# RFID_Brd.net
KiCad netlist of a schematic drawn in EAGLE
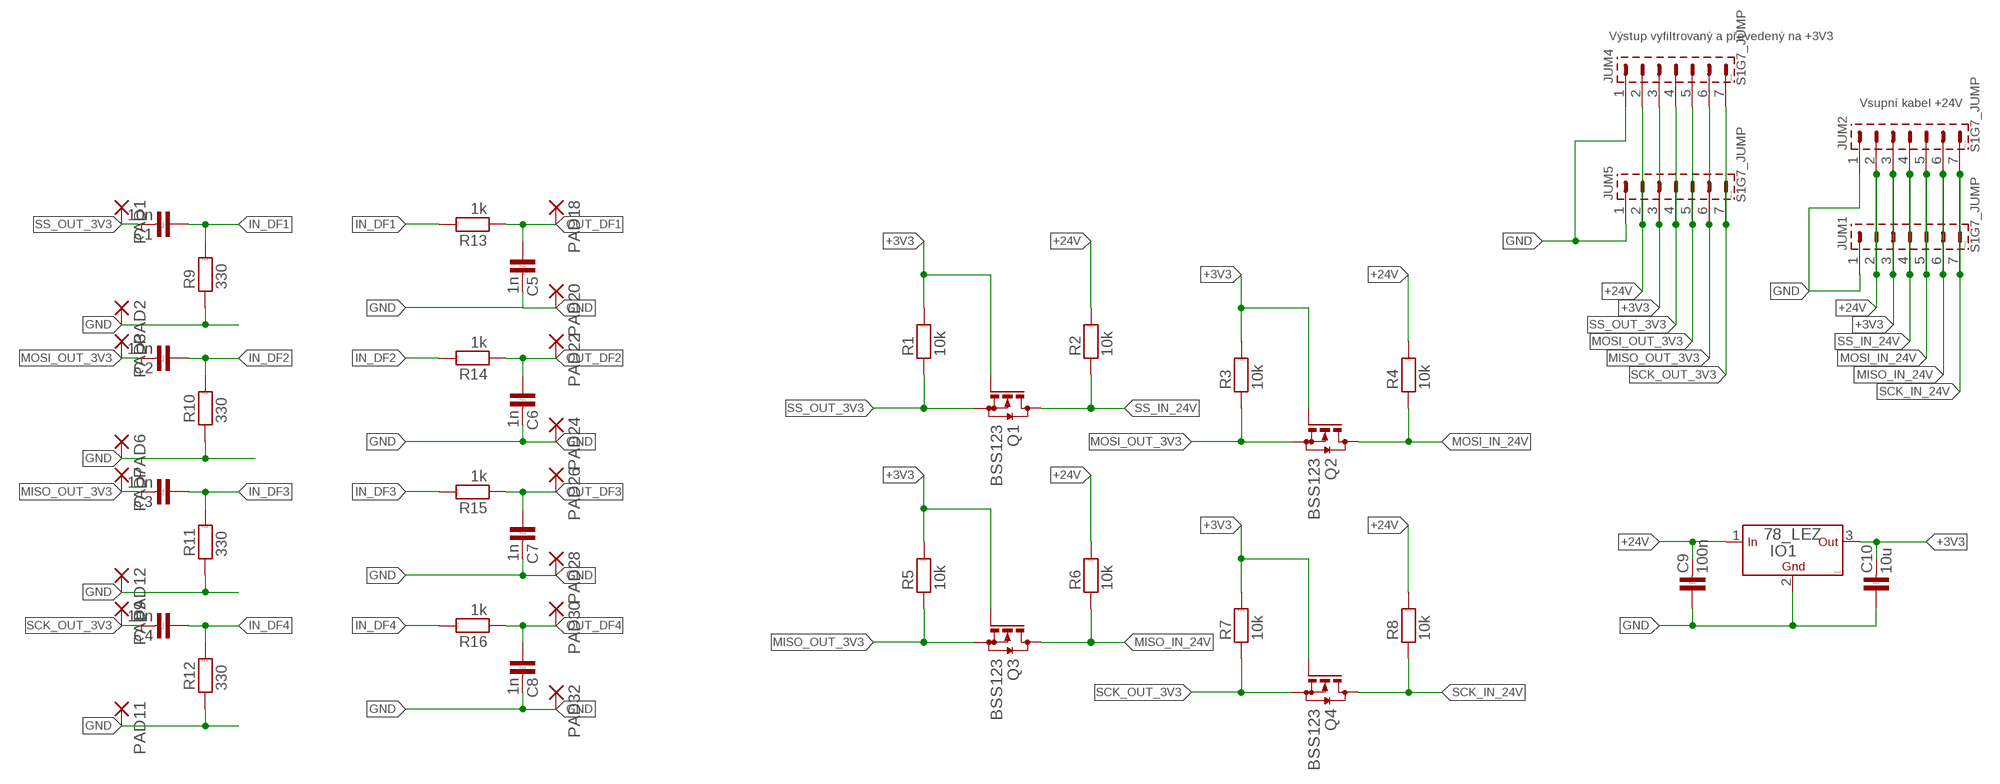
[diagram p0: schematic, sheet 1]

(export (version "E")
  (design (tool "Eeschema 10.0.6"))
  (components
    (comp (ref "C1")
      (value "10n")
      (footprint "eagle-import:1206")
      (libsource (lib "eagle-import") (part "C-KER_1206"))
    )
    (comp (ref "C2")
      (value "10n")
      (footprint "eagle-import:1206")
      (libsource (lib "eagle-import") (part "C-KER_1206"))
    )
    (comp (ref "C3")
      (value "10n")
      (footprint "eagle-import:1206")
      (libsource (lib "eagle-import") (part "C-KER_1206"))
    )
    (comp (ref "C4")
      (value "10n")
      (footprint "eagle-import:1206")
      (libsource (lib "eagle-import") (part "C-KER_1206"))
    )
    (comp (ref "C5")
      (value "1n")
      (footprint "eagle-import:1206")
      (libsource (lib "eagle-import") (part "C-KER_1206"))
    )
    (comp (ref "C6")
      (value "1n")
      (footprint "eagle-import:1206")
      (libsource (lib "eagle-import") (part "C-KER_1206"))
    )
    (comp (ref "C7")
      (value "1n")
      (footprint "eagle-import:1206")
      (libsource (lib "eagle-import") (part "C-KER_1206"))
    )
    (comp (ref "C8")
      (value "1n")
      (footprint "eagle-import:1206")
      (libsource (lib "eagle-import") (part "C-KER_1206"))
    )
    (comp (ref "C9")
      (value "100n")
      (footprint "eagle-import:1206")
      (libsource (lib "eagle-import") (part "C-KER_1206"))
    )
    (comp (ref "C10")
      (value "10u")
      (footprint "eagle-import:1206")
      (libsource (lib "eagle-import") (part "C-KER_1206"))
    )
    (comp (ref "IO1")
      (value "78_LEZ")
      (footprint "eagle-import:TO-220")
      (libsource (lib "eagle-import") (part "78?_LEZ"))
    )
    (comp (ref "JUM1")
      (value "S1G7_JUMP")
      (footprint "eagle-import:S1G7_JUM")
      (libsource (lib "eagle-import") (part "S1G7_JUMP"))
    )
    (comp (ref "JUM2")
      (value "S1G7_JUMP")
      (footprint "eagle-import:S1G7_JUM")
      (libsource (lib "eagle-import") (part "S1G7_JUMP"))
    )
    (comp (ref "JUM4")
      (value "S1G7_JUMP")
      (footprint "eagle-import:S1G7_JUM")
      (libsource (lib "eagle-import") (part "S1G7_JUMP"))
    )
    (comp (ref "JUM5")
      (value "S1G7_JUMP")
      (footprint "eagle-import:S1G7_JUM")
      (libsource (lib "eagle-import") (part "S1G7_JUMP"))
    )
    (comp (ref "PAD1")
      (value "SMD2")
      (footprint "eagle-import:SMD1,27-2,54")
      (libsource (lib "eagle-import") (part "SMD2"))
    )
    (comp (ref "PAD2")
      (value "SMD2")
      (footprint "eagle-import:SMD1,27-2,54")
      (libsource (lib "eagle-import") (part "SMD2"))
    )
    (comp (ref "PAD3")
      (value "SMD2")
      (footprint "eagle-import:SMD1,27-2,54")
      (libsource (lib "eagle-import") (part "SMD2"))
    )
    (comp (ref "PAD6")
      (value "SMD2")
      (footprint "eagle-import:SMD1,27-2,54")
      (libsource (lib "eagle-import") (part "SMD2"))
    )
    (comp (ref "PAD7")
      (value "SMD2")
      (footprint "eagle-import:SMD1,27-2,54")
      (libsource (lib "eagle-import") (part "SMD2"))
    )
    (comp (ref "PAD9")
      (value "SMD2")
      (footprint "eagle-import:SMD1,27-2,54")
      (libsource (lib "eagle-import") (part "SMD2"))
    )
    (comp (ref "PAD11")
      (value "SMD2")
      (footprint "eagle-import:SMD1,27-2,54")
      (libsource (lib "eagle-import") (part "SMD2"))
    )
    (comp (ref "PAD12")
      (value "SMD2")
      (footprint "eagle-import:SMD1,27-2,54")
      (libsource (lib "eagle-import") (part "SMD2"))
    )
    (comp (ref "PAD18")
      (value "SMD2")
      (footprint "eagle-import:SMD1,27-2,54")
      (libsource (lib "eagle-import") (part "SMD2"))
    )
    (comp (ref "PAD20")
      (value "SMD2")
      (footprint "eagle-import:SMD1,27-2,54")
      (libsource (lib "eagle-import") (part "SMD2"))
    )
    (comp (ref "PAD22")
      (value "SMD2")
      (footprint "eagle-import:SMD1,27-2,54")
      (libsource (lib "eagle-import") (part "SMD2"))
    )
    (comp (ref "PAD24")
      (value "SMD2")
      (footprint "eagle-import:SMD1,27-2,54")
      (libsource (lib "eagle-import") (part "SMD2"))
    )
    (comp (ref "PAD26")
      (value "SMD2")
      (footprint "eagle-import:SMD1,27-2,54")
      (libsource (lib "eagle-import") (part "SMD2"))
    )
    (comp (ref "PAD28")
      (value "SMD2")
      (footprint "eagle-import:SMD1,27-2,54")
      (libsource (lib "eagle-import") (part "SMD2"))
    )
    (comp (ref "PAD30")
      (value "SMD2")
      (footprint "eagle-import:SMD1,27-2,54")
      (libsource (lib "eagle-import") (part "SMD2"))
    )
    (comp (ref "PAD32")
      (value "SMD2")
      (footprint "eagle-import:SMD1,27-2,54")
      (libsource (lib "eagle-import") (part "SMD2"))
    )
    (comp (ref "Q1")
      (value "BSS123")
      (footprint "eagle-import:SOT23")
      (libsource (lib "eagle-import") (part "BSS123"))
    )
    (comp (ref "Q2")
      (value "BSS123")
      (footprint "eagle-import:SOT23")
      (libsource (lib "eagle-import") (part "BSS123"))
    )
    (comp (ref "Q3")
      (value "BSS123")
      (footprint "eagle-import:SOT23")
      (libsource (lib "eagle-import") (part "BSS123"))
    )
    (comp (ref "Q4")
      (value "BSS123")
      (footprint "eagle-import:SOT23")
      (libsource (lib "eagle-import") (part "BSS123"))
    )
    (comp (ref "R1")
      (value "10k")
      (footprint "eagle-import:1206")
      (libsource (lib "eagle-import") (part "R_1206"))
    )
    (comp (ref "R2")
      (value "10k")
      (footprint "eagle-import:1206")
      (libsource (lib "eagle-import") (part "R_1206"))
    )
    (comp (ref "R3")
      (value "10k")
      (footprint "eagle-import:1206")
      (libsource (lib "eagle-import") (part "R_1206"))
    )
    (comp (ref "R4")
      (value "10k")
      (footprint "eagle-import:1206")
      (libsource (lib "eagle-import") (part "R_1206"))
    )
    (comp (ref "R5")
      (value "10k")
      (footprint "eagle-import:1206")
      (libsource (lib "eagle-import") (part "R_1206"))
    )
    (comp (ref "R6")
      (value "10k")
      (footprint "eagle-import:1206")
      (libsource (lib "eagle-import") (part "R_1206"))
    )
    (comp (ref "R7")
      (value "10k")
      (footprint "eagle-import:1206")
      (libsource (lib "eagle-import") (part "R_1206"))
    )
    (comp (ref "R8")
      (value "10k")
      (footprint "eagle-import:1206")
      (libsource (lib "eagle-import") (part "R_1206"))
    )
    (comp (ref "R9")
      (value "330")
      (footprint "eagle-import:1206")
      (libsource (lib "eagle-import") (part "R_1206"))
    )
    (comp (ref "R10")
      (value "330")
      (footprint "eagle-import:1206")
      (libsource (lib "eagle-import") (part "R_1206"))
    )
    (comp (ref "R11")
      (value "330")
      (footprint "eagle-import:1206")
      (libsource (lib "eagle-import") (part "R_1206"))
    )
    (comp (ref "R12")
      (value "330")
      (footprint "eagle-import:1206")
      (libsource (lib "eagle-import") (part "R_1206"))
    )
    (comp (ref "R13")
      (value "1k")
      (footprint "eagle-import:1206")
      (libsource (lib "eagle-import") (part "R_1206"))
    )
    (comp (ref "R14")
      (value "1k")
      (footprint "eagle-import:1206")
      (libsource (lib "eagle-import") (part "R_1206"))
    )
    (comp (ref "R15")
      (value "1k")
      (footprint "eagle-import:1206")
      (libsource (lib "eagle-import") (part "R_1206"))
    )
    (comp (ref "R16")
      (value "1k")
      (footprint "eagle-import:1206")
      (libsource (lib "eagle-import") (part "R_1206"))
    )
  )
  (nets
    (net (code "1") (name "+3V3") (class "Default")
      (node (ref "C10") (pin "2") (pinfunction "2_2") (pintype "passive"))
      (node (ref "IO1") (pin "3") (pinfunction "OUT_3") (pintype "passive"))
      (node (ref "JUM1") (pin "3") (pinfunction "3_3") (pintype "passive"))
      (node (ref "JUM2") (pin "3") (pinfunction "3_3") (pintype "passive"))
      (node (ref "JUM4") (pin "3") (pinfunction "3_3") (pintype "passive"))
      (node (ref "JUM5") (pin "3") (pinfunction "3_3") (pintype "passive"))
      (node (ref "Q1") (pin "1") (pinfunction "G_1") (pintype "passive"))
      (node (ref "Q2") (pin "1") (pinfunction "G_1") (pintype "passive"))
      (node (ref "Q3") (pin "1") (pinfunction "G_1") (pintype "passive"))
      (node (ref "Q4") (pin "1") (pinfunction "G_1") (pintype "passive"))
      (node (ref "R1") (pin "2") (pinfunction "2_2") (pintype "passive"))
      (node (ref "R3") (pin "2") (pinfunction "2_2") (pintype "passive"))
      (node (ref "R5") (pin "2") (pinfunction "2_2") (pintype "passive"))
      (node (ref "R7") (pin "2") (pinfunction "2_2") (pintype "passive"))
    )
    (net (code "2") (name "+24V") (class "Default")
      (node (ref "C9") (pin "2") (pinfunction "2_2") (pintype "passive"))
      (node (ref "IO1") (pin "1") (pinfunction "IN_1") (pintype "passive"))
      (node (ref "JUM1") (pin "2") (pinfunction "2_2") (pintype "passive"))
      (node (ref "JUM2") (pin "2") (pinfunction "2_2") (pintype "passive"))
      (node (ref "JUM4") (pin "2") (pinfunction "2_2") (pintype "passive"))
      (node (ref "JUM5") (pin "2") (pinfunction "2_2") (pintype "passive"))
      (node (ref "R2") (pin "2") (pinfunction "2_2") (pintype "passive"))
      (node (ref "R4") (pin "2") (pinfunction "2_2") (pintype "passive"))
      (node (ref "R6") (pin "2") (pinfunction "2_2") (pintype "passive"))
      (node (ref "R8") (pin "2") (pinfunction "2_2") (pintype "passive"))
    )
    (net (code "3") (name "GND") (class "Default")
      (node (ref "C10") (pin "1") (pinfunction "1_1") (pintype "passive"))
      (node (ref "C5") (pin "2") (pinfunction "2_2") (pintype "passive"))
      (node (ref "C6") (pin "2") (pinfunction "2_2") (pintype "passive"))
      (node (ref "C7") (pin "2") (pinfunction "2_2") (pintype "passive"))
      (node (ref "C8") (pin "2") (pinfunction "2_2") (pintype "passive"))
      (node (ref "C9") (pin "1") (pinfunction "1_1") (pintype "passive"))
      (node (ref "IO1") (pin "2") (pinfunction "GND_2") (pintype "passive"))
      (node (ref "JUM1") (pin "1") (pinfunction "1_1") (pintype "passive"))
      (node (ref "JUM2") (pin "1") (pinfunction "1_1") (pintype "passive"))
      (node (ref "JUM4") (pin "1") (pinfunction "1_1") (pintype "passive"))
      (node (ref "JUM5") (pin "1") (pinfunction "1_1") (pintype "passive"))
      (node (ref "PAD11") (pin "1") (pinfunction "P_1") (pintype "passive"))
      (node (ref "PAD12") (pin "1") (pinfunction "P_1") (pintype "passive"))
      (node (ref "PAD2") (pin "1") (pinfunction "P_1") (pintype "passive"))
      (node (ref "PAD20") (pin "1") (pinfunction "P_1") (pintype "passive"))
      (node (ref "PAD24") (pin "1") (pinfunction "P_1") (pintype "passive"))
      (node (ref "PAD28") (pin "1") (pinfunction "P_1") (pintype "passive"))
      (node (ref "PAD32") (pin "1") (pinfunction "P_1") (pintype "passive"))
      (node (ref "PAD6") (pin "1") (pinfunction "P_1") (pintype "passive"))
      (node (ref "R10") (pin "1") (pinfunction "1_1") (pintype "passive"))
      (node (ref "R11") (pin "1") (pinfunction "1_1") (pintype "passive"))
      (node (ref "R12") (pin "1") (pinfunction "1_1") (pintype "passive"))
      (node (ref "R9") (pin "1") (pinfunction "1_1") (pintype "passive"))
    )
    (net (code "4") (name "IN_DF1") (class "Default")
      (node (ref "C1") (pin "1") (pinfunction "1_1") (pintype "passive"))
      (node (ref "R13") (pin "2") (pinfunction "2_2") (pintype "passive"))
      (node (ref "R9") (pin "2") (pinfunction "2_2") (pintype "passive"))
    )
    (net (code "5") (name "IN_DF2") (class "Default")
      (node (ref "C2") (pin "1") (pinfunction "1_1") (pintype "passive"))
      (node (ref "R10") (pin "2") (pinfunction "2_2") (pintype "passive"))
      (node (ref "R14") (pin "2") (pinfunction "2_2") (pintype "passive"))
    )
    (net (code "6") (name "IN_DF3") (class "Default")
      (node (ref "C3") (pin "1") (pinfunction "1_1") (pintype "passive"))
      (node (ref "R11") (pin "2") (pinfunction "2_2") (pintype "passive"))
      (node (ref "R15") (pin "2") (pinfunction "2_2") (pintype "passive"))
    )
    (net (code "7") (name "IN_DF4") (class "Default")
      (node (ref "C4") (pin "1") (pinfunction "1_1") (pintype "passive"))
      (node (ref "R12") (pin "2") (pinfunction "2_2") (pintype "passive"))
      (node (ref "R16") (pin "2") (pinfunction "2_2") (pintype "passive"))
    )
    (net (code "8") (name "MISO_IN_24V") (class "Default")
      (node (ref "JUM1") (pin "6") (pinfunction "6_6") (pintype "passive"))
      (node (ref "JUM2") (pin "6") (pinfunction "6_6") (pintype "passive"))
      (node (ref "Q3") (pin "3") (pinfunction "D_3") (pintype "passive"))
      (node (ref "R6") (pin "1") (pinfunction "1_1") (pintype "passive"))
    )
    (net (code "9") (name "MISO_OUT_3V3") (class "Default")
      (node (ref "C3") (pin "2") (pinfunction "2_2") (pintype "passive"))
      (node (ref "JUM4") (pin "6") (pinfunction "6_6") (pintype "passive"))
      (node (ref "JUM5") (pin "6") (pinfunction "6_6") (pintype "passive"))
      (node (ref "PAD7") (pin "1") (pinfunction "P_1") (pintype "passive"))
      (node (ref "Q3") (pin "2") (pinfunction "S_2") (pintype "passive"))
      (node (ref "R5") (pin "1") (pinfunction "1_1") (pintype "passive"))
    )
    (net (code "10") (name "MOSI_IN_24V") (class "Default")
      (node (ref "JUM1") (pin "5") (pinfunction "5_5") (pintype "passive"))
      (node (ref "JUM2") (pin "5") (pinfunction "5_5") (pintype "passive"))
      (node (ref "Q2") (pin "3") (pinfunction "D_3") (pintype "passive"))
      (node (ref "R4") (pin "1") (pinfunction "1_1") (pintype "passive"))
    )
    (net (code "11") (name "MOSI_OUT_3V3") (class "Default")
      (node (ref "C2") (pin "2") (pinfunction "2_2") (pintype "passive"))
      (node (ref "JUM4") (pin "5") (pinfunction "5_5") (pintype "passive"))
      (node (ref "JUM5") (pin "5") (pinfunction "5_5") (pintype "passive"))
      (node (ref "PAD3") (pin "1") (pinfunction "P_1") (pintype "passive"))
      (node (ref "Q2") (pin "2") (pinfunction "S_2") (pintype "passive"))
      (node (ref "R3") (pin "1") (pinfunction "1_1") (pintype "passive"))
    )
    (net (code "12") (name "OUT_DF1") (class "Default")
      (node (ref "C5") (pin "1") (pinfunction "1_1") (pintype "passive"))
      (node (ref "PAD18") (pin "1") (pinfunction "P_1") (pintype "passive"))
      (node (ref "R13") (pin "1") (pinfunction "1_1") (pintype "passive"))
    )
    (net (code "13") (name "OUT_DF2") (class "Default")
      (node (ref "C6") (pin "1") (pinfunction "1_1") (pintype "passive"))
      (node (ref "PAD22") (pin "1") (pinfunction "P_1") (pintype "passive"))
      (node (ref "R14") (pin "1") (pinfunction "1_1") (pintype "passive"))
    )
    (net (code "14") (name "OUT_DF3") (class "Default")
      (node (ref "C7") (pin "1") (pinfunction "1_1") (pintype "passive"))
      (node (ref "PAD26") (pin "1") (pinfunction "P_1") (pintype "passive"))
      (node (ref "R15") (pin "1") (pinfunction "1_1") (pintype "passive"))
    )
    (net (code "15") (name "OUT_DF4") (class "Default")
      (node (ref "C8") (pin "1") (pinfunction "1_1") (pintype "passive"))
      (node (ref "PAD30") (pin "1") (pinfunction "P_1") (pintype "passive"))
      (node (ref "R16") (pin "1") (pinfunction "1_1") (pintype "passive"))
    )
    (net (code "16") (name "SCK_IN_24V") (class "Default")
      (node (ref "JUM1") (pin "7") (pinfunction "7_7") (pintype "passive"))
      (node (ref "JUM2") (pin "7") (pinfunction "7_7") (pintype "passive"))
      (node (ref "Q4") (pin "3") (pinfunction "D_3") (pintype "passive"))
      (node (ref "R8") (pin "1") (pinfunction "1_1") (pintype "passive"))
    )
    (net (code "17") (name "SCK_OUT_3V3") (class "Default")
      (node (ref "C4") (pin "2") (pinfunction "2_2") (pintype "passive"))
      (node (ref "JUM4") (pin "7") (pinfunction "7_7") (pintype "passive"))
      (node (ref "JUM5") (pin "7") (pinfunction "7_7") (pintype "passive"))
      (node (ref "PAD9") (pin "1") (pinfunction "P_1") (pintype "passive"))
      (node (ref "Q4") (pin "2") (pinfunction "S_2") (pintype "passive"))
      (node (ref "R7") (pin "1") (pinfunction "1_1") (pintype "passive"))
    )
    (net (code "18") (name "SS_IN_24V") (class "Default")
      (node (ref "JUM1") (pin "4") (pinfunction "4_4") (pintype "passive"))
      (node (ref "JUM2") (pin "4") (pinfunction "4_4") (pintype "passive"))
      (node (ref "Q1") (pin "3") (pinfunction "D_3") (pintype "passive"))
      (node (ref "R2") (pin "1") (pinfunction "1_1") (pintype "passive"))
    )
    (net (code "19") (name "SS_OUT_3V3") (class "Default")
      (node (ref "C1") (pin "2") (pinfunction "2_2") (pintype "passive"))
      (node (ref "JUM4") (pin "4") (pinfunction "4_4") (pintype "passive"))
      (node (ref "JUM5") (pin "4") (pinfunction "4_4") (pintype "passive"))
      (node (ref "PAD1") (pin "1") (pinfunction "P_1") (pintype "passive"))
      (node (ref "Q1") (pin "2") (pinfunction "S_2") (pintype "passive"))
      (node (ref "R1") (pin "1") (pinfunction "1_1") (pintype "passive"))
    )
  )
)
